# ERPIHAT01.net
KiCad netlist of a schematic drawn in EAGLE
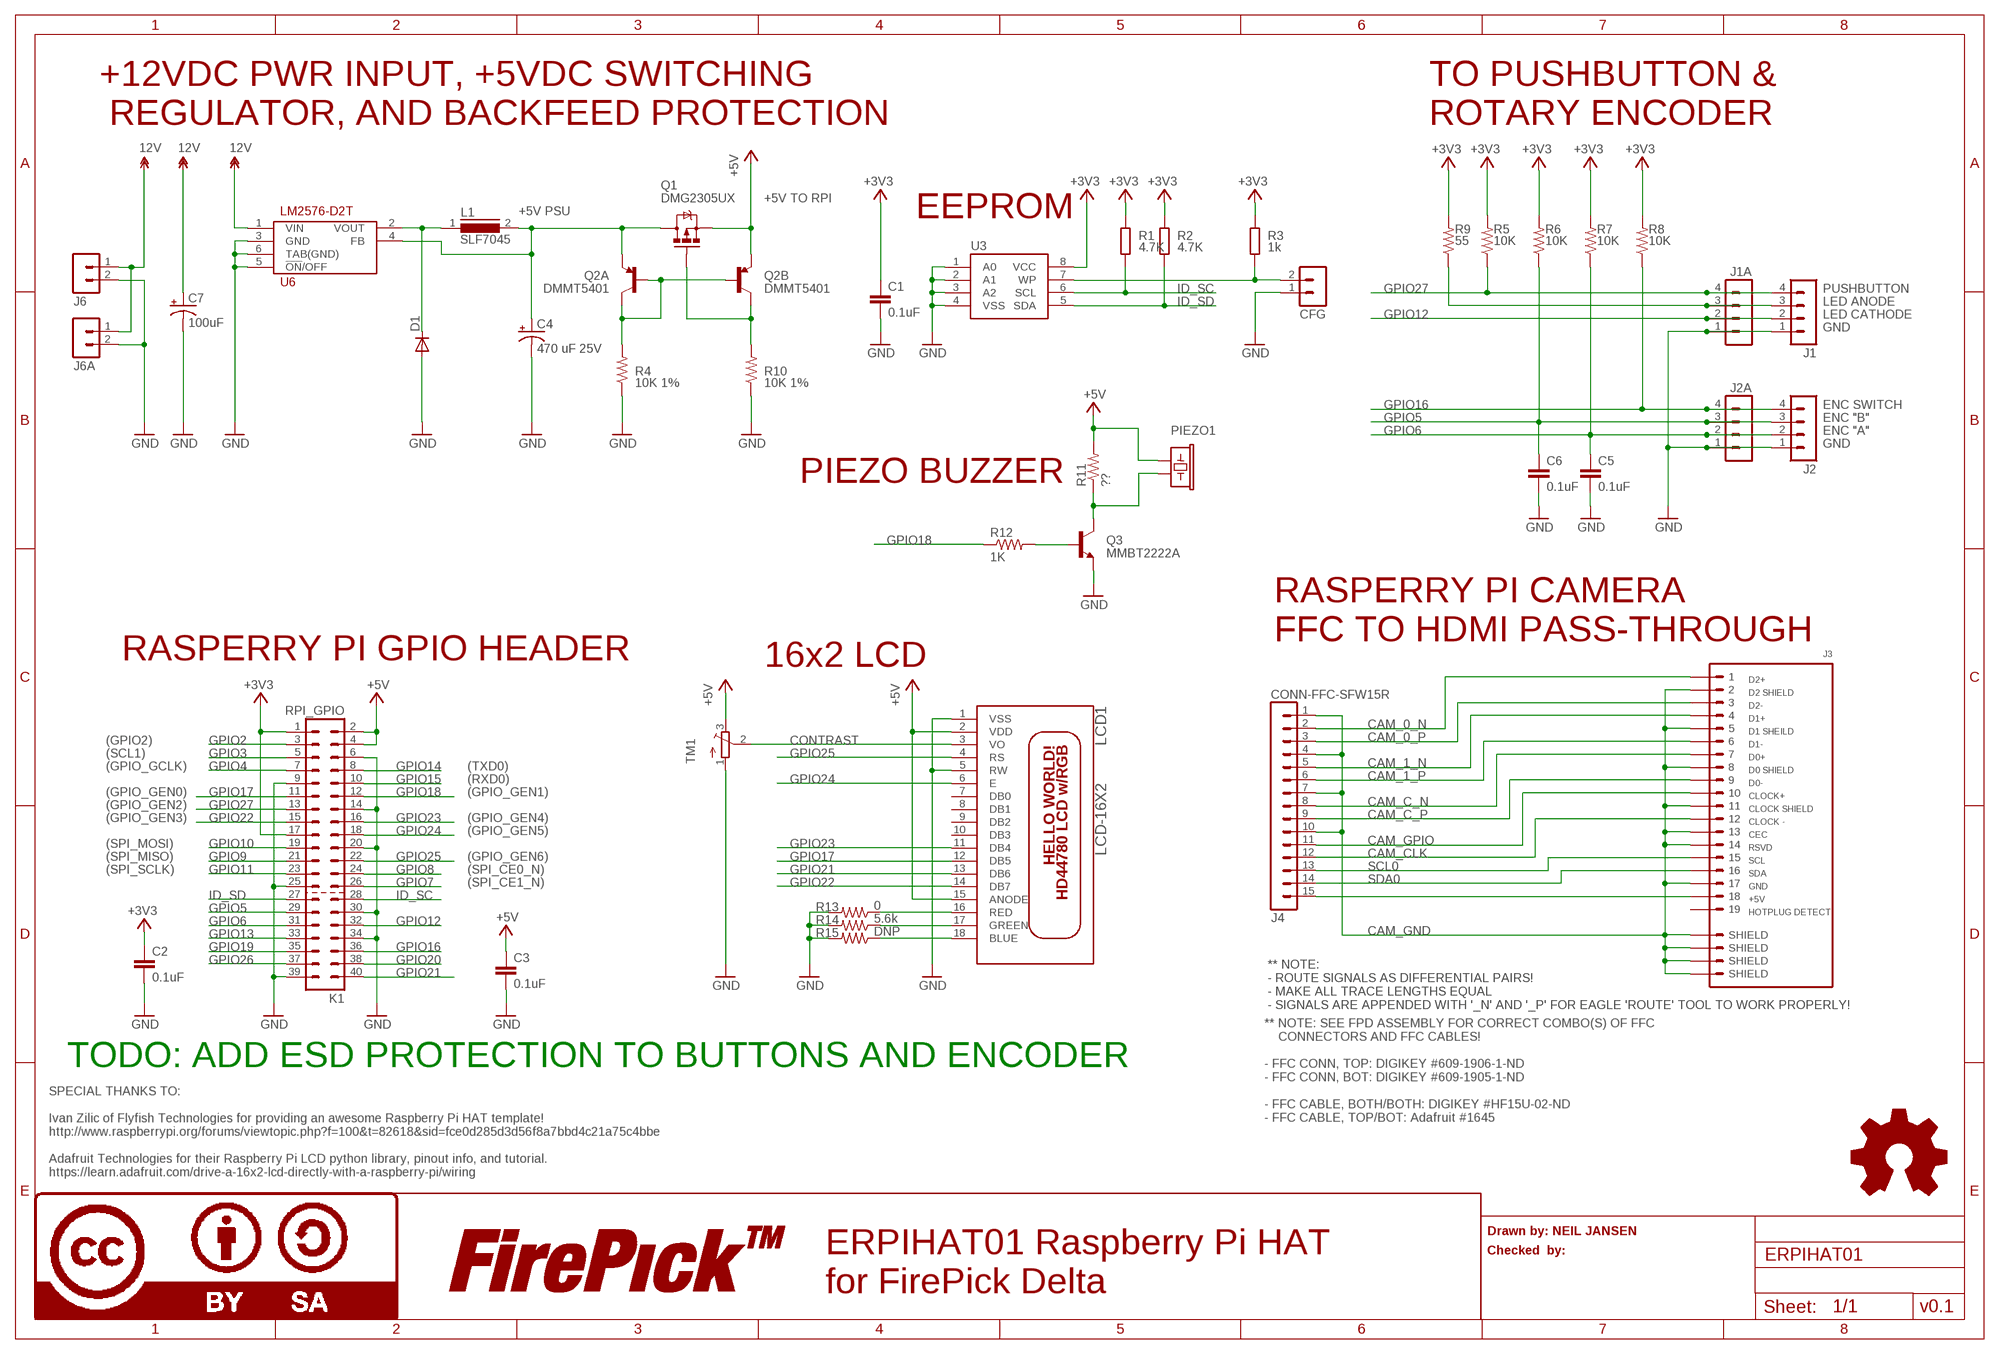
[diagram p0: schematic, sheet 1]

(export (version "E")
  (design (tool "Eeschema 10.0.6"))
  (components
    (comp (ref "C1")
      (value "0.1uF")
      (footprint "eagle-import:C0805K")
      (libsource (lib "eagle-import") (part "C-EUC0805K"))
    )
    (comp (ref "C2")
      (value "0.1uF")
      (footprint "eagle-import:C0805K")
      (libsource (lib "eagle-import") (part "C-EUC0805K"))
    )
    (comp (ref "C3")
      (value "0.1uF")
      (footprint "eagle-import:C0805K")
      (libsource (lib "eagle-import") (part "C-EUC0805K"))
    )
    (comp (ref "C4")
      (value "470 uF 25V")
      (footprint "eagle-import:PANASONIC_D")
      (libsource (lib "eagle-import") (part "CPOL-USD"))
    )
    (comp (ref "C5")
      (value "0.1uF")
      (footprint "eagle-import:0805")
      (libsource (lib "eagle-import") (part "CAP0805"))
    )
    (comp (ref "C6")
      (value "0.1uF")
      (footprint "eagle-import:0805")
      (libsource (lib "eagle-import") (part "CAP0805"))
    )
    (comp (ref "C7")
      (value "100uF")
      (footprint "eagle-import:PANASONIC_D")
      (libsource (lib "eagle-import") (part "CPOL-USD"))
    )
    (comp (ref "CFG")
      (value "MA02-1")
      (footprint "eagle-import:MA02-1")
      (libsource (lib "eagle-import") (part "MA02-1"))
    )
    (comp (ref "D1")
      (value "DIODE-DO-214AC")
      (footprint "eagle-import:DO-214AC")
      (libsource (lib "eagle-import") (part "DIODE-DO-214AC"))
    )
    (comp (ref "J1")
      (value "CONN-RECT-4PINJST-PH-2MM")
      (footprint "eagle-import:CONN-JST-PH_2.0MM_4PIN-SMT-RA")
      (libsource (lib "eagle-import") (part "CONN-RECT-4PINJST-PH-2MM"))
    )
    (comp (ref "J1A")
      (value "MA04-1")
      (footprint "eagle-import:MA04-1")
      (libsource (lib "eagle-import") (part "MA04-1"))
    )
    (comp (ref "J2")
      (value "CONN-RECT-4PINJST-PH-2MM")
      (footprint "eagle-import:CONN-JST-PH_2.0MM_4PIN-SMT-RA")
      (libsource (lib "eagle-import") (part "CONN-RECT-4PINJST-PH-2MM"))
    )
    (comp (ref "J2A")
      (value "MA04-1")
      (footprint "eagle-import:MA04-1")
      (libsource (lib "eagle-import") (part "MA04-1"))
    )
    (comp (ref "J3")
      (value "CONN-HDMI")
      (footprint "eagle-import:CON-HDMI-FCI-10029449-001RLF")
      (libsource (lib "eagle-import") (part "CONN-HDMI"))
    )
    (comp (ref "J4")
      (value "CONN-FFC-SFW15R")
      (footprint "eagle-import:CON-FFC-SFW15R")
      (libsource (lib "eagle-import") (part "CONN-FFC-SFW15R"))
    )
    (comp (ref "J6")
      (value "CONN-RECT-2PIN")
      (footprint "eagle-import:CONN-JST_PH-2.0MM-2PIN-SMT-RA")
      (libsource (lib "eagle-import") (part "CONN-RECT-2PIN"))
    )
    (comp (ref "J6A")
      (value "MA02-1")
      (footprint "eagle-import:MA02-1")
      (libsource (lib "eagle-import") (part "MA02-1"))
    )
    (comp (ref "K1")
      (value "RPI_GPIO")
      (footprint "eagle-import:PIN_20X2")
      (libsource (lib "eagle-import") (part "PIN20X2"))
    )
    (comp (ref "L1")
      (value "SLF7045")
      (footprint "eagle-import:SLF7045")
      (libsource (lib "eagle-import") (part "SLF7045"))
    )
    (comp (ref "LCD1")
      (value "LCD-16X2")
      (footprint "eagle-import:LCD-16X2")
      (libsource (lib "eagle-import") (part "LCD-16X2"))
    )
    (comp (ref "LOGO1")
      (value "LOGO-FIREPICK")
      (footprint "eagle-import:LOGO-FIREPICK")
      (libsource (lib "eagle-import") (part "LOGO-FIREPICK"))
    )
    (comp (ref "LOGO2")
      (value "LOGO-OSHWMEDIUM")
      (footprint "eagle-import:LOGO-OSHW-MEDIUM")
      (libsource (lib "eagle-import") (part "LOGO-OSHWMEDIUM"))
    )
    (comp (ref "LOGO3")
      (value "LOGO-CC-BY-SA")
      (footprint "eagle-import:LOGO-CC-BY-SA")
      (libsource (lib "eagle-import") (part "LOGO-CC-BY-SA"))
    )
    (comp (ref "PIEZO1")
      (value "BUZZERPTH")
      (footprint "eagle-import:BUZZER-12MM")
      (libsource (lib "eagle-import") (part "BUZZERPTH"))
    )
    (comp (ref "Q1")
      (value "DMG2305UX")
      (footprint "eagle-import:SOT23-3")
      (libsource (lib "eagle-import") (part "MOSFET-PCHANNEL"))
    )
    (comp (ref "Q2")
      (value "DMMT5401")
      (footprint "eagle-import:SOT23-6")
      (libsource (lib "eagle-import") (part "DMMT5401"))
    )
    (comp (ref "Q3")
      (value "MMBT2222A")
      (footprint "eagle-import:SOT23-3")
      (libsource (lib "eagle-import") (part "TRANSISTOR_NPNMMBT2222A"))
    )
    (comp (ref "R1")
      (value "4.7K")
      (footprint "eagle-import:M0805")
      (fields (field (name "TOLERANCE") "5%"))
      (libsource (lib "eagle-import") (part "R-EU_M0805"))
    )
    (comp (ref "R2")
      (value "4.7K")
      (footprint "eagle-import:M0805")
      (fields (field (name "TOLERANCE") "5%"))
      (libsource (lib "eagle-import") (part "R-EU_M0805"))
    )
    (comp (ref "R3")
      (value "1k")
      (footprint "eagle-import:M0805")
      (fields (field (name "TOLERANCE") "5%"))
      (libsource (lib "eagle-import") (part "R-EU_M0805"))
    )
    (comp (ref "R4")
      (value "10K 1%")
      (footprint "eagle-import:0805")
      (libsource (lib "eagle-import") (part "RESISTOR0805-RES"))
    )
    (comp (ref "R5")
      (value "10K")
      (footprint "eagle-import:0805")
      (libsource (lib "eagle-import") (part "RESISTOR0805-RES"))
    )
    (comp (ref "R6")
      (value "10K")
      (footprint "eagle-import:0805")
      (libsource (lib "eagle-import") (part "RESISTOR0805-RES"))
    )
    (comp (ref "R7")
      (value "10K")
      (footprint "eagle-import:0805")
      (libsource (lib "eagle-import") (part "RESISTOR0805-RES"))
    )
    (comp (ref "R8")
      (value "10K")
      (footprint "eagle-import:0805")
      (libsource (lib "eagle-import") (part "RESISTOR0805-RES"))
    )
    (comp (ref "R9")
      (value "55")
      (footprint "eagle-import:0805")
      (libsource (lib "eagle-import") (part "RESISTOR0805-RES"))
    )
    (comp (ref "R10")
      (value "10K 1%")
      (footprint "eagle-import:0805")
      (libsource (lib "eagle-import") (part "RESISTOR0805-RES"))
    )
    (comp (ref "R11")
      (value "??")
      (footprint "eagle-import:0805")
      (libsource (lib "eagle-import") (part "RESISTOR0805-RES"))
    )
    (comp (ref "R12")
      (value "1K")
      (footprint "eagle-import:0805")
      (libsource (lib "eagle-import") (part "RESISTOR0805-RES"))
    )
    (comp (ref "R13")
      (value "0")
      (footprint "eagle-import:0805")
      (libsource (lib "eagle-import") (part "RESISTOR0805-RES"))
    )
    (comp (ref "R14")
      (value "5.6k")
      (footprint "eagle-import:0805")
      (libsource (lib "eagle-import") (part "RESISTOR0805-RES"))
    )
    (comp (ref "R15")
      (value "DNP")
      (footprint "eagle-import:0805")
      (libsource (lib "eagle-import") (part "RESISTOR0805-RES"))
    )
    (comp (ref "TM1")
      (value "TRIMPOTTC33X")
      (footprint "eagle-import:TC33X")
      (libsource (lib "eagle-import") (part "TRIMPOTTC33X"))
    )
    (comp (ref "U3")
      (value "EEPROM-I2CEIAJ")
      (footprint "eagle-import:SO08-EIAJ")
      (libsource (lib "eagle-import") (part "EEPROM-I2CEIAJ"))
    )
    (comp (ref "U6")
      (value "LM2576-D2T")
      (footprint "eagle-import:D2PAK")
      (libsource (lib "eagle-import") (part "LM2576-D2T"))
    )
  )
  (nets
    (net (code "1") (name "+3V3") (class "Default")
      (node (ref "C1") (pin "1") (pinfunction "1_1") (pintype "passive"))
      (node (ref "C2") (pin "1") (pinfunction "1_1") (pintype "passive"))
      (node (ref "K1") (pin "1") (pinfunction "1_1") (pintype "passive"))
      (node (ref "K1") (pin "17") (pinfunction "17_17") (pintype "passive"))
      (node (ref "R1") (pin "2") (pinfunction "2_2") (pintype "passive"))
      (node (ref "R2") (pin "2") (pinfunction "2_2") (pintype "passive"))
      (node (ref "R3") (pin "2") (pinfunction "2_2") (pintype "passive"))
      (node (ref "R5") (pin "2") (pinfunction "2_2") (pintype "passive"))
      (node (ref "R6") (pin "2") (pinfunction "2_2") (pintype "passive"))
      (node (ref "R7") (pin "2") (pinfunction "2_2") (pintype "passive"))
      (node (ref "R8") (pin "2") (pinfunction "2_2") (pintype "passive"))
      (node (ref "R9") (pin "2") (pinfunction "2_2") (pintype "passive"))
      (node (ref "U3") (pin "8") (pinfunction "VCC_8") (pintype "power_in"))
    )
    (net (code "2") (name "+5V") (class "Default")
      (node (ref "C3") (pin "1") (pinfunction "1_1") (pintype "passive"))
      (node (ref "K1") (pin "2") (pinfunction "2_2") (pintype "passive"))
      (node (ref "K1") (pin "4") (pinfunction "4_4") (pintype "passive"))
      (node (ref "LCD1") (pin "15") (pinfunction "ANODE_15") (pintype "input"))
      (node (ref "LCD1") (pin "2") (pinfunction "VDD_2") (pintype "power_in"))
      (node (ref "PIEZO1") (pin "+") (pinfunction "1_+") (pintype "passive"))
      (node (ref "Q1") (pin "2") (pinfunction "S_2") (pintype "passive"))
      (node (ref "Q2") (pin "5") (pinfunction "E_5") (pintype "passive"))
      (node (ref "R11") (pin "2") (pinfunction "2_2") (pintype "passive"))
      (node (ref "TM1") (pin "3") (pinfunction "E_3") (pintype "passive"))
    )
    (net (code "3") (name "/CAM_0_N") (class "Default")
      (node (ref "J3") (pin "1") (pinfunction "1_1") (pintype "passive"))
      (node (ref "J4") (pin "2") (pinfunction "2_2") (pintype "passive"))
    )
    (net (code "4") (name "/CAM_0_P") (class "Default")
      (node (ref "J3") (pin "3") (pinfunction "3_3") (pintype "passive"))
      (node (ref "J4") (pin "3") (pinfunction "3_3") (pintype "passive"))
    )
    (net (code "5") (name "/CAM_1_N") (class "Default")
      (node (ref "J3") (pin "4") (pinfunction "4_4") (pintype "passive"))
      (node (ref "J4") (pin "5") (pinfunction "5_5") (pintype "passive"))
    )
    (net (code "6") (name "/CAM_1_P") (class "Default")
      (node (ref "J3") (pin "6") (pinfunction "6_6") (pintype "passive"))
      (node (ref "J4") (pin "6") (pinfunction "6_6") (pintype "passive"))
    )
    (net (code "7") (name "/CAM_C_N") (class "Default")
      (node (ref "J3") (pin "7") (pinfunction "7_7") (pintype "passive"))
      (node (ref "J4") (pin "8") (pinfunction "8_8") (pintype "passive"))
    )
    (net (code "8") (name "/CAM_C_P") (class "Default")
      (node (ref "J3") (pin "9") (pinfunction "9_9") (pintype "passive"))
      (node (ref "J4") (pin "9") (pinfunction "9_9") (pintype "passive"))
    )
    (net (code "9") (name "/CAM_GND") (class "Default")
      (node (ref "J3") (pin "11") (pinfunction "11_11") (pintype "passive"))
      (node (ref "J3") (pin "13") (pinfunction "13_13") (pintype "passive"))
      (node (ref "J3") (pin "14") (pinfunction "14_14") (pintype "passive"))
      (node (ref "J3") (pin "17") (pinfunction "17_17") (pintype "passive"))
      (node (ref "J3") (pin "2") (pinfunction "2_2") (pintype "passive"))
      (node (ref "J3") (pin "5") (pinfunction "5_5") (pintype "passive"))
      (node (ref "J3") (pin "8") (pinfunction "8_8") (pintype "passive"))
      (node (ref "J3") (pin "SHIELD1") (pinfunction "SHIELD_SHIELD1") (pintype "passive"))
      (node (ref "J3") (pin "SHIELD2") (pinfunction "SHIELD_SHIELD2") (pintype "passive"))
      (node (ref "J3") (pin "SHIELD3") (pinfunction "SHIELD_SHIELD3") (pintype "passive"))
      (node (ref "J3") (pin "SHIELD4") (pinfunction "SHIELD_SHIELD4") (pintype "passive"))
      (node (ref "J4") (pin "1") (pinfunction "1_1") (pintype "passive"))
      (node (ref "J4") (pin "10") (pinfunction "10_10") (pintype "passive"))
      (node (ref "J4") (pin "4") (pinfunction "4_4") (pintype "passive"))
      (node (ref "J4") (pin "7") (pinfunction "7_7") (pintype "passive"))
    )
    (net (code "10") (name "/CONTRAST") (class "Default")
      (node (ref "LCD1") (pin "3") (pinfunction "VO_3") (pintype "input"))
      (node (ref "TM1") (pin "2") (pinfunction "S_2") (pintype "passive"))
    )
    (net (code "11") (name "/GPIO2") (class "Default")
      (node (ref "K1") (pin "3") (pinfunction "3_3") (pintype "passive"))
    )
    (net (code "12") (name "/GPIO3") (class "Default")
      (node (ref "K1") (pin "5") (pinfunction "5_5") (pintype "passive"))
    )
    (net (code "13") (name "/GPIO4") (class "Default")
      (node (ref "K1") (pin "7") (pinfunction "7_7") (pintype "passive"))
    )
    (net (code "14") (name "/GPIO5") (class "Default")
      (node (ref "C6") (pin "1") (pinfunction "1_1") (pintype "passive"))
      (node (ref "J2") (pin "3") (pinfunction "3_3") (pintype "passive"))
      (node (ref "J2A") (pin "3") (pinfunction "3_3") (pintype "passive"))
      (node (ref "K1") (pin "29") (pinfunction "29_29") (pintype "passive"))
      (node (ref "R6") (pin "1") (pinfunction "1_1") (pintype "passive"))
    )
    (net (code "15") (name "/GPIO6") (class "Default")
      (node (ref "C5") (pin "1") (pinfunction "1_1") (pintype "passive"))
      (node (ref "J2") (pin "2") (pinfunction "2_2") (pintype "passive"))
      (node (ref "J2A") (pin "2") (pinfunction "2_2") (pintype "passive"))
      (node (ref "K1") (pin "31") (pinfunction "31_31") (pintype "passive"))
      (node (ref "R7") (pin "1") (pinfunction "1_1") (pintype "passive"))
    )
    (net (code "16") (name "/GPIO7") (class "Default")
      (node (ref "K1") (pin "26") (pinfunction "26_26") (pintype "passive"))
    )
    (net (code "17") (name "/GPIO8") (class "Default")
      (node (ref "K1") (pin "24") (pinfunction "24_24") (pintype "passive"))
    )
    (net (code "18") (name "/GPIO9") (class "Default")
      (node (ref "K1") (pin "21") (pinfunction "21_21") (pintype "passive"))
    )
    (net (code "19") (name "/GPIO10") (class "Default")
      (node (ref "K1") (pin "19") (pinfunction "19_19") (pintype "passive"))
    )
    (net (code "20") (name "/GPIO11") (class "Default")
      (node (ref "K1") (pin "23") (pinfunction "23_23") (pintype "passive"))
    )
    (net (code "21") (name "/GPIO12") (class "Default")
      (node (ref "J1") (pin "2") (pinfunction "2_2") (pintype "passive"))
      (node (ref "J1A") (pin "2") (pinfunction "2_2") (pintype "passive"))
      (node (ref "K1") (pin "32") (pinfunction "32_32") (pintype "passive"))
    )
    (net (code "22") (name "/GPIO13") (class "Default")
      (node (ref "K1") (pin "33") (pinfunction "33_33") (pintype "passive"))
    )
    (net (code "23") (name "/GPIO14") (class "Default")
      (node (ref "K1") (pin "8") (pinfunction "8_8") (pintype "passive"))
    )
    (net (code "24") (name "/GPIO15") (class "Default")
      (node (ref "K1") (pin "10") (pinfunction "10_10") (pintype "passive"))
    )
    (net (code "25") (name "/GPIO16") (class "Default")
      (node (ref "J2") (pin "4") (pinfunction "4_4") (pintype "passive"))
      (node (ref "J2A") (pin "4") (pinfunction "4_4") (pintype "passive"))
      (node (ref "K1") (pin "36") (pinfunction "36_36") (pintype "passive"))
      (node (ref "R8") (pin "1") (pinfunction "1_1") (pintype "passive"))
    )
    (net (code "26") (name "/GPIO17") (class "Default")
      (node (ref "K1") (pin "11") (pinfunction "11_11") (pintype "passive"))
      (node (ref "LCD1") (pin "12") (pinfunction "DB5_12") (pintype "bidirectional"))
    )
    (net (code "27") (name "/GPIO18") (class "Default")
      (node (ref "K1") (pin "12") (pinfunction "12_12") (pintype "passive"))
      (node (ref "R12") (pin "1") (pinfunction "1_1") (pintype "passive"))
    )
    (net (code "28") (name "/GPIO19") (class "Default")
      (node (ref "K1") (pin "35") (pinfunction "35_35") (pintype "passive"))
    )
    (net (code "29") (name "/GPIO20") (class "Default")
      (node (ref "K1") (pin "38") (pinfunction "38_38") (pintype "passive"))
    )
    (net (code "30") (name "/GPIO21") (class "Default")
      (node (ref "K1") (pin "40") (pinfunction "40_40") (pintype "passive"))
      (node (ref "LCD1") (pin "13") (pinfunction "DB6_13") (pintype "bidirectional"))
    )
    (net (code "31") (name "/GPIO22") (class "Default")
      (node (ref "K1") (pin "15") (pinfunction "15_15") (pintype "passive"))
      (node (ref "LCD1") (pin "14") (pinfunction "DB7_14") (pintype "bidirectional"))
    )
    (net (code "32") (name "/GPIO23") (class "Default")
      (node (ref "K1") (pin "16") (pinfunction "16_16") (pintype "passive"))
      (node (ref "LCD1") (pin "11") (pinfunction "DB4_11") (pintype "bidirectional"))
    )
    (net (code "33") (name "/GPIO24") (class "Default")
      (node (ref "K1") (pin "18") (pinfunction "18_18") (pintype "passive"))
      (node (ref "LCD1") (pin "6") (pinfunction "E_6") (pintype "input"))
    )
    (net (code "34") (name "/GPIO25") (class "Default")
      (node (ref "K1") (pin "22") (pinfunction "22_22") (pintype "passive"))
      (node (ref "LCD1") (pin "4") (pinfunction "RS_4") (pintype "input"))
    )
    (net (code "35") (name "/GPIO26") (class "Default")
      (node (ref "K1") (pin "37") (pinfunction "37_37") (pintype "passive"))
    )
    (net (code "36") (name "/GPIO27") (class "Default")
      (node (ref "J1") (pin "4") (pinfunction "4_4") (pintype "passive"))
      (node (ref "J1A") (pin "4") (pinfunction "4_4") (pintype "passive"))
      (node (ref "K1") (pin "13") (pinfunction "13_13") (pintype "passive"))
      (node (ref "R5") (pin "1") (pinfunction "1_1") (pintype "passive"))
    )
    (net (code "37") (name "/ID_SC") (class "Default")
      (node (ref "K1") (pin "28") (pinfunction "28_28") (pintype "passive"))
      (node (ref "R1") (pin "1") (pinfunction "1_1") (pintype "passive"))
      (node (ref "U3") (pin "6") (pinfunction "SCL_6") (pintype "bidirectional"))
    )
    (net (code "38") (name "/ID_SD") (class "Default")
      (node (ref "K1") (pin "27") (pinfunction "27_27") (pintype "passive"))
      (node (ref "R2") (pin "1") (pinfunction "1_1") (pintype "passive"))
      (node (ref "U3") (pin "5") (pinfunction "SDA_5") (pintype "bidirectional"))
    )
    (net (code "39") (name "12V") (class "Default")
      (node (ref "C7") (pin "+") (pinfunction "+_+") (pintype "passive"))
      (node (ref "J6") (pin "1") (pinfunction "1_1") (pintype "passive"))
      (node (ref "J6A") (pin "1") (pinfunction "1_1") (pintype "passive"))
      (node (ref "U6") (pin "1") (pinfunction "VIN_1") (pintype "power_in"))
    )
    (net (code "40") (name "GND") (class "Default")
      (node (ref "C1") (pin "2") (pinfunction "2_2") (pintype "passive"))
      (node (ref "C2") (pin "2") (pinfunction "2_2") (pintype "passive"))
      (node (ref "C3") (pin "2") (pinfunction "2_2") (pintype "passive"))
      (node (ref "C4") (pin "-") (pinfunction "-_-") (pintype "passive"))
      (node (ref "C5") (pin "2") (pinfunction "2_2") (pintype "passive"))
      (node (ref "C6") (pin "2") (pinfunction "2_2") (pintype "passive"))
      (node (ref "C7") (pin "-") (pinfunction "-_-") (pintype "passive"))
      (node (ref "CFG") (pin "1") (pinfunction "1_1") (pintype "passive"))
      (node (ref "D1") (pin "A") (pinfunction "A_A") (pintype "passive"))
      (node (ref "J1") (pin "1") (pinfunction "1_1") (pintype "passive"))
      (node (ref "J1A") (pin "1") (pinfunction "1_1") (pintype "passive"))
      (node (ref "J2") (pin "1") (pinfunction "1_1") (pintype "passive"))
      (node (ref "J2A") (pin "1") (pinfunction "1_1") (pintype "passive"))
      (node (ref "J6") (pin "2") (pinfunction "2_2") (pintype "passive"))
      (node (ref "J6A") (pin "2") (pinfunction "2_2") (pintype "passive"))
      (node (ref "K1") (pin "14") (pinfunction "14_14") (pintype "passive"))
      (node (ref "K1") (pin "20") (pinfunction "20_20") (pintype "passive"))
      (node (ref "K1") (pin "25") (pinfunction "25_25") (pintype "passive"))
      (node (ref "K1") (pin "30") (pinfunction "30_30") (pintype "passive"))
      (node (ref "K1") (pin "34") (pinfunction "34_34") (pintype "passive"))
      (node (ref "K1") (pin "39") (pinfunction "39_39") (pintype "passive"))
      (node (ref "K1") (pin "6") (pinfunction "6_6") (pintype "passive"))
      (node (ref "K1") (pin "9") (pinfunction "9_9") (pintype "passive"))
      (node (ref "LCD1") (pin "1") (pinfunction "VSS_1") (pintype "power_in"))
      (node (ref "LCD1") (pin "5") (pinfunction "RW_5") (pintype "input"))
      (node (ref "Q3") (pin "2") (pinfunction "E_2") (pintype "passive"))
      (node (ref "R10") (pin "1") (pinfunction "1_1") (pintype "passive"))
      (node (ref "R13") (pin "2") (pinfunction "2_2") (pintype "passive"))
      (node (ref "R14") (pin "2") (pinfunction "2_2") (pintype "passive"))
      (node (ref "R15") (pin "2") (pinfunction "2_2") (pintype "passive"))
      (node (ref "R4") (pin "1") (pinfunction "1_1") (pintype "passive"))
      (node (ref "TM1") (pin "1") (pinfunction "A_1") (pintype "passive"))
      (node (ref "U3") (pin "1") (pinfunction "A0_1") (pintype "bidirectional"))
      (node (ref "U3") (pin "2") (pinfunction "A1_2") (pintype "bidirectional"))
      (node (ref "U3") (pin "3") (pinfunction "A2_3") (pintype "bidirectional"))
      (node (ref "U3") (pin "4") (pinfunction "VSS_4") (pintype "power_in"))
      (node (ref "U6") (pin "3") (pinfunction "GND_3") (pintype "power_in"))
      (node (ref "U6") (pin "5") (pinfunction "~{ON}/OFF_5") (pintype "bidirectional"))
      (node (ref "U6") (pin "6") (pinfunction "TAB(GND)_6") (pintype "bidirectional"))
    )
    (net (code "41") (name "Net-(J1-Pad3)") (class "Default")
      (node (ref "J1") (pin "3") (pinfunction "3_3") (pintype "passive"))
      (node (ref "J1A") (pin "3") (pinfunction "3_3") (pintype "passive"))
      (node (ref "R9") (pin "1") (pinfunction "1_1") (pintype "passive"))
    )
    (net (code "42") (name "Net-(J3-Pad10)") (class "Default")
      (node (ref "J3") (pin "10") (pinfunction "10_10") (pintype "passive"))
      (node (ref "J4") (pin "11") (pinfunction "11_11") (pintype "passive"))
    )
    (net (code "43") (name "Net-(J3-Pad12)") (class "Default")
      (node (ref "J3") (pin "12") (pinfunction "12_12") (pintype "passive"))
      (node (ref "J4") (pin "12") (pinfunction "12_12") (pintype "passive"))
    )
    (net (code "44") (name "Net-(J3-Pad15)") (class "Default")
      (node (ref "J3") (pin "15") (pinfunction "15_15") (pintype "passive"))
      (node (ref "J4") (pin "13") (pinfunction "13_13") (pintype "passive"))
    )
    (net (code "45") (name "Net-(J3-Pad16)") (class "Default")
      (node (ref "J3") (pin "16") (pinfunction "16_16") (pintype "passive"))
      (node (ref "J4") (pin "14") (pinfunction "14_14") (pintype "passive"))
    )
    (net (code "46") (name "Net-(J3-Pad18)") (class "Default")
      (node (ref "J3") (pin "18") (pinfunction "18_18") (pintype "passive"))
      (node (ref "J4") (pin "15") (pinfunction "15_15") (pintype "passive"))
    )
    (net (code "47") (name "Net-(LCD1-BLUE)") (class "Default")
      (node (ref "LCD1") (pin "18") (pinfunction "BLUE_18") (pintype "input"))
      (node (ref "R15") (pin "1") (pinfunction "1_1") (pintype "passive"))
    )
    (net (code "48") (name "Net-(LCD1-GREEN)") (class "Default")
      (node (ref "LCD1") (pin "17") (pinfunction "GREEN_17") (pintype "input"))
      (node (ref "R14") (pin "1") (pinfunction "1_1") (pintype "passive"))
    )
    (net (code "49") (name "Net-(LCD1-RED)") (class "Default")
      (node (ref "LCD1") (pin "16") (pinfunction "RED_16") (pintype "input"))
      (node (ref "R13") (pin "1") (pinfunction "1_1") (pintype "passive"))
    )
    (net (code "50") (name "Net-(PIEZO1-2)") (class "Default")
      (node (ref "PIEZO1") (pin "-") (pinfunction "2_-") (pintype "passive"))
      (node (ref "Q3") (pin "3") (pinfunction "C_3") (pintype "passive"))
      (node (ref "R11") (pin "1") (pinfunction "1_1") (pintype "passive"))
    )
    (net (code "51") (name "Net-(Q1-D)") (class "Default")
      (node (ref "C4") (pin "+") (pinfunction "+_+") (pintype "passive"))
      (node (ref "L1") (pin "2") (pinfunction "2_2") (pintype "passive"))
      (node (ref "Q1") (pin "3") (pinfunction "D_3") (pintype "passive"))
      (node (ref "Q2") (pin "6") (pinfunction "E_6") (pintype "passive"))
      (node (ref "U6") (pin "4") (pinfunction "FB_4") (pintype "input"))
    )
    (net (code "52") (name "Net-(Q1-G)") (class "Default")
      (node (ref "Q1") (pin "1") (pinfunction "G_1") (pintype "passive"))
      (node (ref "Q2") (pin "4") (pinfunction "C_4") (pintype "passive"))
      (node (ref "R10") (pin "2") (pinfunction "2_2") (pintype "passive"))
    )
    (net (code "53") (name "Net-(Q2A-B)") (class "Default")
      (node (ref "Q2") (pin "1") (pinfunction "C_1") (pintype "passive"))
      (node (ref "Q2") (pin "2") (pinfunction "B_2") (pintype "passive"))
      (node (ref "Q2") (pin "3") (pinfunction "B_3") (pintype "passive"))
      (node (ref "R4") (pin "2") (pinfunction "2_2") (pintype "passive"))
    )
    (net (code "54") (name "Net-(Q3-B)") (class "Default")
      (node (ref "Q3") (pin "1") (pinfunction "B_1") (pintype "passive"))
      (node (ref "R12") (pin "2") (pinfunction "2_2") (pintype "passive"))
    )
    (net (code "55") (name "Net-(U3-WP)") (class "Default")
      (node (ref "CFG") (pin "2") (pinfunction "2_2") (pintype "passive"))
      (node (ref "R3") (pin "1") (pinfunction "1_1") (pintype "passive"))
      (node (ref "U3") (pin "7") (pinfunction "WP_7") (pintype "bidirectional"))
    )
    (net (code "56") (name "Net-(U6-VOUT)") (class "Default")
      (node (ref "D1") (pin "C") (pinfunction "C_C") (pintype "passive"))
      (node (ref "L1") (pin "1") (pinfunction "1_1") (pintype "passive"))
      (node (ref "U6") (pin "2") (pinfunction "VOUT_2") (pintype "power_in"))
    )
    (net (code "57") (name "unconnected-(J3-Pad19)") (class "Default")
      (node (ref "J3") (pin "19") (pinfunction "19_19") (pintype "passive"))
    )
    (net (code "58") (name "unconnected-(LCD1-DB0-Pad7)") (class "Default")
      (node (ref "LCD1") (pin "7") (pinfunction "DB0_7") (pintype "bidirectional"))
    )
    (net (code "59") (name "unconnected-(LCD1-DB1-Pad8)") (class "Default")
      (node (ref "LCD1") (pin "8") (pinfunction "DB1_8") (pintype "bidirectional"))
    )
    (net (code "60") (name "unconnected-(LCD1-DB2-Pad9)") (class "Default")
      (node (ref "LCD1") (pin "9") (pinfunction "DB2_9") (pintype "bidirectional"))
    )
    (net (code "61") (name "unconnected-(LCD1-DB3-Pad10)") (class "Default")
      (node (ref "LCD1") (pin "10") (pinfunction "DB3_10") (pintype "bidirectional"))
    )
  )
)
